# STM32F412VEx-Core.net
KiCad netlist of a schematic drawn in EasyEDA Pro
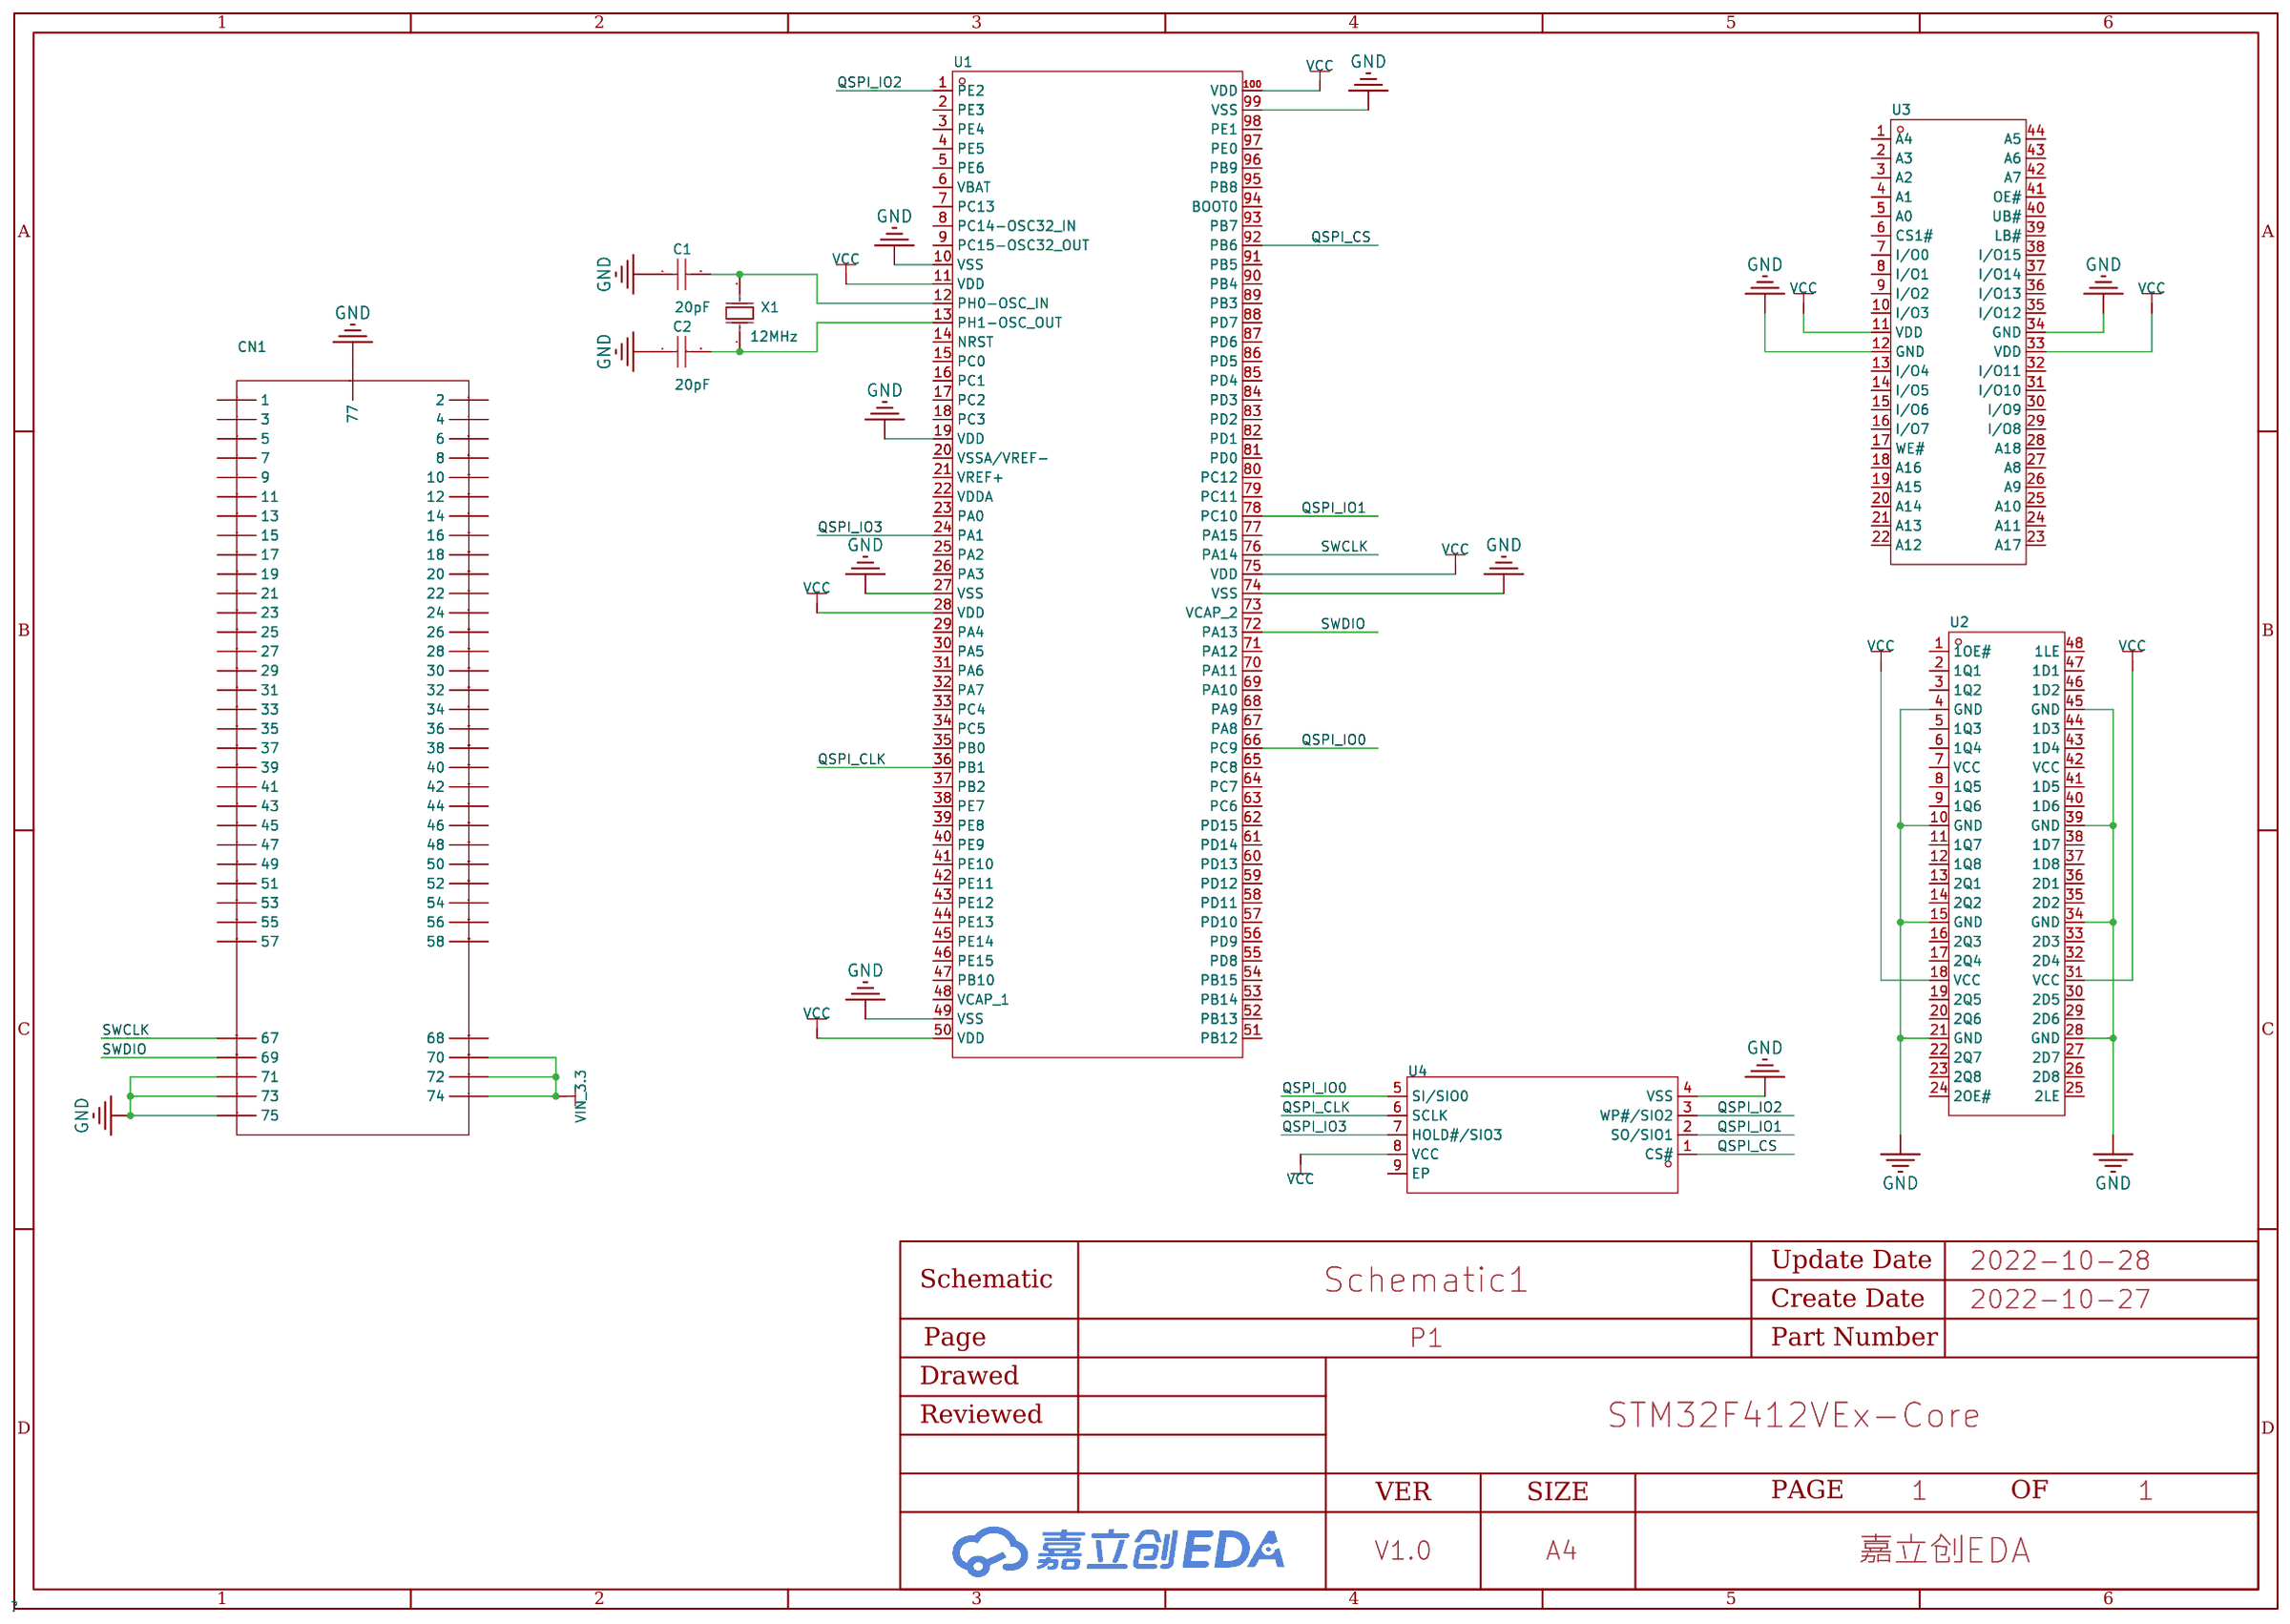
[diagram p0: schematic sheet]

(export (version "E")
  (design (tool "Eeschema 10.0.6"))
  (components
    (comp (ref "C1")
      (value "20pF")
      (footprint "easyedapro:C0402")
      (description "温度系数:C0G;容值:20pF;精度:±5%;额定电压:50V;")
      (fields (field (name "Manufacturer Part") "0402CG200J500NT") (field (name "Manufacturer") "FH(风华)"))
      (libsource (lib "easyedapro") (part "0402CG200J500NT"))
    )
    (comp (ref "C2")
      (value "20pF")
      (footprint "easyedapro:C0402")
      (description "温度系数:C0G;容值:20pF;精度:±5%;额定电压:50V;")
      (fields (field (name "Manufacturer Part") "0402CG200J500NT") (field (name "Manufacturer") "FH(风华)"))
      (libsource (lib "easyedapro") (part "0402CG200J500NT"))
    )
    (comp (ref "CN1")
      (value "~")
      (footprint "easyedapro:M.2_67P_0.5mm_M-key")
      (libsource (lib "easyedapro") (part "M.2_67P_0.5mm_M-key"))
    )
    (comp (ref "U1")
      (value "STM32F412VET6")
      (footprint "easyedapro:LQFP-100_L14.0-W14.0-P0.50-LS16.0-BL")
      (fields (field (name "Manufacturer") "ST(意法半导体)"))
      (libsource (lib "easyedapro") (part "STM32F412VET6"))
    )
    (comp (ref "U2")
      (value "SN74ALVCH16373DGGR")
      (footprint "easyedapro:TSSOP-48_L12.6-W6.2-P0.50-LS8.1-BL")
      (description "系列:74ALVCH;逻辑类型:D 型透明锁存器;输出类型:三态;电压-电源:1.65V ~ 3.6V;")
      (fields (field (name "Manufacturer") "TI(德州仪器)"))
      (libsource (lib "easyedapro") (part "SN74ALVCH16373DGGR"))
    )
    (comp (ref "U3")
      (value "IS62WV51216EBLL-45TLI")
      (footprint "easyedapro:TSOPII-44_L18.4-W10.2-P0.80-LS11.8-BL")
      (fields (field (name "Manufacturer") "ISSI(美国芯成)"))
      (libsource (lib "easyedapro") (part "IS62WV51216EBLL-45TLI"))
    )
    (comp (ref "U4")
      (value "XT26Q01DWSIGA")
      (footprint "easyedapro:WSON-8_L8.0-W6.0-P1.27-TL-EP-1")
      (fields (field (name "Manufacturer") "XTX(芯天下)"))
      (libsource (lib "easyedapro") (part "XT26Q01DWSIGA"))
    )
    (comp (ref "X1")
      (value "12MHz")
      (footprint "easyedapro:OSC-SMD_L5.0-W3.2")
      (description "晶振类型:贴片无源晶振;频率:12MHz;频率公差:±10ppm;频率稳定度:±50ppm;负载电容:20pF;工作温度:-40~+85;")
      (fields (field (name "Manufacturer Part") "X503212MSB2GI") (field (name "Manufacturer") "YXC(扬兴晶振)"))
      (libsource (lib "easyedapro") (part "X503212MSB2GI"))
    )
  )
  (nets
    (net (code "1") (name "/QSPI_CLK") (class "Default")
      (node (ref "U1") (pin "36") (pinfunction "PB1_36") (pintype "input"))
      (node (ref "U4") (pin "6") (pinfunction "SCLK_6") (pintype "input"))
    )
    (net (code "2") (name "/QSPI_CS") (class "Default")
      (node (ref "U1") (pin "92") (pinfunction "PB6_92") (pintype "input"))
      (node (ref "U4") (pin "1") (pinfunction "CS#_1") (pintype "input"))
    )
    (net (code "3") (name "/QSPI_IO0") (class "Default")
      (node (ref "U1") (pin "66") (pinfunction "PC9_66") (pintype "input"))
      (node (ref "U4") (pin "5") (pinfunction "SI/SIO0_5") (pintype "input"))
    )
    (net (code "4") (name "/QSPI_IO1") (class "Default")
      (node (ref "U1") (pin "78") (pinfunction "PC10_78") (pintype "input"))
      (node (ref "U4") (pin "2") (pinfunction "SO/SIO1_2") (pintype "input"))
    )
    (net (code "5") (name "/QSPI_IO2") (class "Default")
      (node (ref "U1") (pin "1") (pinfunction "PE2_1") (pintype "input"))
      (node (ref "U4") (pin "3") (pinfunction "WP#/SIO2_3") (pintype "input"))
    )
    (net (code "6") (name "/QSPI_IO3") (class "Default")
      (node (ref "U1") (pin "24") (pinfunction "PA1_24") (pintype "input"))
      (node (ref "U4") (pin "7") (pinfunction "HOLD#/SIO3_7") (pintype "input"))
    )
    (net (code "7") (name "/SWCLK") (class "Default")
      (node (ref "CN1") (pin "67") (pinfunction "67_67") (pintype "input"))
      (node (ref "U1") (pin "76") (pinfunction "PA14_76") (pintype "input"))
    )
    (net (code "8") (name "/SWDIO") (class "Default")
      (node (ref "CN1") (pin "69") (pinfunction "69_69") (pintype "input"))
      (node (ref "U1") (pin "72") (pinfunction "PA13_72") (pintype "input"))
    )
    (net (code "9") (name "GND") (class "Default")
      (node (ref "C1") (pin "1") (pinfunction "1_1") (pintype "input"))
      (node (ref "C2") (pin "1") (pinfunction "1_1") (pintype "input"))
      (node (ref "CN1") (pin "71") (pinfunction "71_71") (pintype "input"))
      (node (ref "CN1") (pin "73") (pinfunction "73_73") (pintype "input"))
      (node (ref "CN1") (pin "75") (pinfunction "75_75") (pintype "input"))
      (node (ref "CN1") (pin "77") (pinfunction "77_77") (pintype "input"))
      (node (ref "U1") (pin "10") (pinfunction "VSS_10") (pintype "input"))
      (node (ref "U1") (pin "19") (pinfunction "VDD_19") (pintype "input"))
      (node (ref "U1") (pin "27") (pinfunction "VSS_27") (pintype "input"))
      (node (ref "U1") (pin "49") (pinfunction "VSS_49") (pintype "input"))
      (node (ref "U1") (pin "74") (pinfunction "VSS_74") (pintype "input"))
      (node (ref "U1") (pin "99") (pinfunction "VSS_99") (pintype "input"))
      (node (ref "U2") (pin "10") (pinfunction "GND_10") (pintype "input"))
      (node (ref "U2") (pin "15") (pinfunction "GND_15") (pintype "input"))
      (node (ref "U2") (pin "21") (pinfunction "GND_21") (pintype "input"))
      (node (ref "U2") (pin "28") (pinfunction "GND_28") (pintype "input"))
      (node (ref "U2") (pin "34") (pinfunction "GND_34") (pintype "input"))
      (node (ref "U2") (pin "39") (pinfunction "GND_39") (pintype "input"))
      (node (ref "U2") (pin "4") (pinfunction "GND_4") (pintype "input"))
      (node (ref "U2") (pin "45") (pinfunction "GND_45") (pintype "input"))
      (node (ref "U3") (pin "12") (pinfunction "GND_12") (pintype "input"))
      (node (ref "U3") (pin "34") (pinfunction "GND_34") (pintype "input"))
      (node (ref "U4") (pin "4") (pinfunction "VSS_4") (pintype "input"))
    )
    (net (code "10") (name "Net-(U1-PH0-OSC_IN)") (class "Default")
      (node (ref "C1") (pin "2") (pinfunction "2_2") (pintype "input"))
      (node (ref "U1") (pin "12") (pinfunction "PH0-OSC_IN_12") (pintype "input"))
      (node (ref "X1") (pin "2") (pinfunction "OSC2_2") (pintype "input"))
    )
    (net (code "11") (name "Net-(U1-PH1-OSC_OUT)") (class "Default")
      (node (ref "C2") (pin "2") (pinfunction "2_2") (pintype "input"))
      (node (ref "U1") (pin "13") (pinfunction "PH1-OSC_OUT_13") (pintype "input"))
      (node (ref "X1") (pin "1") (pinfunction "OSC1_1") (pintype "input"))
    )
    (net (code "12") (name "VCC") (class "Default")
      (node (ref "U1") (pin "100") (pinfunction "VDD_100") (pintype "input"))
      (node (ref "U1") (pin "11") (pinfunction "VDD_11") (pintype "input"))
      (node (ref "U1") (pin "28") (pinfunction "VDD_28") (pintype "input"))
      (node (ref "U1") (pin "50") (pinfunction "VDD_50") (pintype "input"))
      (node (ref "U1") (pin "75") (pinfunction "VDD_75") (pintype "input"))
      (node (ref "U2") (pin "18") (pinfunction "VCC_18") (pintype "input"))
      (node (ref "U2") (pin "31") (pinfunction "VCC_31") (pintype "input"))
      (node (ref "U3") (pin "11") (pinfunction "VDD_11") (pintype "input"))
      (node (ref "U3") (pin "33") (pinfunction "VDD_33") (pintype "input"))
      (node (ref "U4") (pin "8") (pinfunction "VCC_8") (pintype "input"))
    )
    (net (code "13") (name "VIN_3.3") (class "Default")
      (node (ref "CN1") (pin "70") (pinfunction "70_70") (pintype "input"))
      (node (ref "CN1") (pin "72") (pinfunction "72_72") (pintype "input"))
      (node (ref "CN1") (pin "74") (pinfunction "74_74") (pintype "input"))
    )
    (net (code "14") (name "unconnected-(CN1-Pad1)") (class "Default")
      (node (ref "CN1") (pin "1") (pinfunction "1_1") (pintype "input"))
    )
    (net (code "15") (name "unconnected-(CN1-Pad2)") (class "Default")
      (node (ref "CN1") (pin "2") (pinfunction "2_2") (pintype "input"))
    )
    (net (code "16") (name "unconnected-(CN1-Pad3)") (class "Default")
      (node (ref "CN1") (pin "3") (pinfunction "3_3") (pintype "input"))
    )
    (net (code "17") (name "unconnected-(CN1-Pad4)") (class "Default")
      (node (ref "CN1") (pin "4") (pinfunction "4_4") (pintype "input"))
    )
    (net (code "18") (name "unconnected-(CN1-Pad5)") (class "Default")
      (node (ref "CN1") (pin "5") (pinfunction "5_5") (pintype "input"))
    )
    (net (code "19") (name "unconnected-(CN1-Pad6)") (class "Default")
      (node (ref "CN1") (pin "6") (pinfunction "6_6") (pintype "input"))
    )
    (net (code "20") (name "unconnected-(CN1-Pad7)") (class "Default")
      (node (ref "CN1") (pin "7") (pinfunction "7_7") (pintype "input"))
    )
    (net (code "21") (name "unconnected-(CN1-Pad8)") (class "Default")
      (node (ref "CN1") (pin "8") (pinfunction "8_8") (pintype "input"))
    )
    (net (code "22") (name "unconnected-(CN1-Pad9)") (class "Default")
      (node (ref "CN1") (pin "9") (pinfunction "9_9") (pintype "input"))
    )
    (net (code "23") (name "unconnected-(CN1-Pad10)") (class "Default")
      (node (ref "CN1") (pin "10") (pinfunction "10_10") (pintype "input"))
    )
    (net (code "24") (name "unconnected-(CN1-Pad11)") (class "Default")
      (node (ref "CN1") (pin "11") (pinfunction "11_11") (pintype "input"))
    )
    (net (code "25") (name "unconnected-(CN1-Pad12)") (class "Default")
      (node (ref "CN1") (pin "12") (pinfunction "12_12") (pintype "input"))
    )
    (net (code "26") (name "unconnected-(CN1-Pad13)") (class "Default")
      (node (ref "CN1") (pin "13") (pinfunction "13_13") (pintype "input"))
    )
    (net (code "27") (name "unconnected-(CN1-Pad14)") (class "Default")
      (node (ref "CN1") (pin "14") (pinfunction "14_14") (pintype "input"))
    )
    (net (code "28") (name "unconnected-(CN1-Pad15)") (class "Default")
      (node (ref "CN1") (pin "15") (pinfunction "15_15") (pintype "input"))
    )
    (net (code "29") (name "unconnected-(CN1-Pad16)") (class "Default")
      (node (ref "CN1") (pin "16") (pinfunction "16_16") (pintype "input"))
    )
    (net (code "30") (name "unconnected-(CN1-Pad17)") (class "Default")
      (node (ref "CN1") (pin "17") (pinfunction "17_17") (pintype "input"))
    )
    (net (code "31") (name "unconnected-(CN1-Pad18)") (class "Default")
      (node (ref "CN1") (pin "18") (pinfunction "18_18") (pintype "input"))
    )
    (net (code "32") (name "unconnected-(CN1-Pad19)") (class "Default")
      (node (ref "CN1") (pin "19") (pinfunction "19_19") (pintype "input"))
    )
    (net (code "33") (name "unconnected-(CN1-Pad20)") (class "Default")
      (node (ref "CN1") (pin "20") (pinfunction "20_20") (pintype "input"))
    )
    (net (code "34") (name "unconnected-(CN1-Pad21)") (class "Default")
      (node (ref "CN1") (pin "21") (pinfunction "21_21") (pintype "input"))
    )
    (net (code "35") (name "unconnected-(CN1-Pad22)") (class "Default")
      (node (ref "CN1") (pin "22") (pinfunction "22_22") (pintype "input"))
    )
    (net (code "36") (name "unconnected-(CN1-Pad23)") (class "Default")
      (node (ref "CN1") (pin "23") (pinfunction "23_23") (pintype "input"))
    )
    (net (code "37") (name "unconnected-(CN1-Pad24)") (class "Default")
      (node (ref "CN1") (pin "24") (pinfunction "24_24") (pintype "input"))
    )
    (net (code "38") (name "unconnected-(CN1-Pad25)") (class "Default")
      (node (ref "CN1") (pin "25") (pinfunction "25_25") (pintype "input"))
    )
    (net (code "39") (name "unconnected-(CN1-Pad26)") (class "Default")
      (node (ref "CN1") (pin "26") (pinfunction "26_26") (pintype "input"))
    )
    (net (code "40") (name "unconnected-(CN1-Pad27)") (class "Default")
      (node (ref "CN1") (pin "27") (pinfunction "27_27") (pintype "input"))
    )
    (net (code "41") (name "unconnected-(CN1-Pad28)") (class "Default")
      (node (ref "CN1") (pin "28") (pinfunction "28_28") (pintype "input"))
    )
    (net (code "42") (name "unconnected-(CN1-Pad29)") (class "Default")
      (node (ref "CN1") (pin "29") (pinfunction "29_29") (pintype "input"))
    )
    (net (code "43") (name "unconnected-(CN1-Pad30)") (class "Default")
      (node (ref "CN1") (pin "30") (pinfunction "30_30") (pintype "input"))
    )
    (net (code "44") (name "unconnected-(CN1-Pad31)") (class "Default")
      (node (ref "CN1") (pin "31") (pinfunction "31_31") (pintype "input"))
    )
    (net (code "45") (name "unconnected-(CN1-Pad32)") (class "Default")
      (node (ref "CN1") (pin "32") (pinfunction "32_32") (pintype "input"))
    )
    (net (code "46") (name "unconnected-(CN1-Pad33)") (class "Default")
      (node (ref "CN1") (pin "33") (pinfunction "33_33") (pintype "input"))
    )
    (net (code "47") (name "unconnected-(CN1-Pad34)") (class "Default")
      (node (ref "CN1") (pin "34") (pinfunction "34_34") (pintype "input"))
    )
    (net (code "48") (name "unconnected-(CN1-Pad35)") (class "Default")
      (node (ref "CN1") (pin "35") (pinfunction "35_35") (pintype "input"))
    )
    (net (code "49") (name "unconnected-(CN1-Pad36)") (class "Default")
      (node (ref "CN1") (pin "36") (pinfunction "36_36") (pintype "input"))
    )
    (net (code "50") (name "unconnected-(CN1-Pad37)") (class "Default")
      (node (ref "CN1") (pin "37") (pinfunction "37_37") (pintype "input"))
    )
    (net (code "51") (name "unconnected-(CN1-Pad38)") (class "Default")
      (node (ref "CN1") (pin "38") (pinfunction "38_38") (pintype "input"))
    )
    (net (code "52") (name "unconnected-(CN1-Pad39)") (class "Default")
      (node (ref "CN1") (pin "39") (pinfunction "39_39") (pintype "input"))
    )
    (net (code "53") (name "unconnected-(CN1-Pad40)") (class "Default")
      (node (ref "CN1") (pin "40") (pinfunction "40_40") (pintype "input"))
    )
    (net (code "54") (name "unconnected-(CN1-Pad41)") (class "Default")
      (node (ref "CN1") (pin "41") (pinfunction "41_41") (pintype "input"))
    )
    (net (code "55") (name "unconnected-(CN1-Pad42)") (class "Default")
      (node (ref "CN1") (pin "42") (pinfunction "42_42") (pintype "input"))
    )
    (net (code "56") (name "unconnected-(CN1-Pad43)") (class "Default")
      (node (ref "CN1") (pin "43") (pinfunction "43_43") (pintype "input"))
    )
    (net (code "57") (name "unconnected-(CN1-Pad44)") (class "Default")
      (node (ref "CN1") (pin "44") (pinfunction "44_44") (pintype "input"))
    )
    (net (code "58") (name "unconnected-(CN1-Pad45)") (class "Default")
      (node (ref "CN1") (pin "45") (pinfunction "45_45") (pintype "input"))
    )
    (net (code "59") (name "unconnected-(CN1-Pad46)") (class "Default")
      (node (ref "CN1") (pin "46") (pinfunction "46_46") (pintype "input"))
    )
    (net (code "60") (name "unconnected-(CN1-Pad47)") (class "Default")
      (node (ref "CN1") (pin "47") (pinfunction "47_47") (pintype "input"))
    )
    (net (code "61") (name "unconnected-(CN1-Pad48)") (class "Default")
      (node (ref "CN1") (pin "48") (pinfunction "48_48") (pintype "input"))
    )
    (net (code "62") (name "unconnected-(CN1-Pad49)") (class "Default")
      (node (ref "CN1") (pin "49") (pinfunction "49_49") (pintype "input"))
    )
    (net (code "63") (name "unconnected-(CN1-Pad50)") (class "Default")
      (node (ref "CN1") (pin "50") (pinfunction "50_50") (pintype "input"))
    )
    (net (code "64") (name "unconnected-(CN1-Pad51)") (class "Default")
      (node (ref "CN1") (pin "51") (pinfunction "51_51") (pintype "input"))
    )
    (net (code "65") (name "unconnected-(CN1-Pad52)") (class "Default")
      (node (ref "CN1") (pin "52") (pinfunction "52_52") (pintype "input"))
    )
    (net (code "66") (name "unconnected-(CN1-Pad53)") (class "Default")
      (node (ref "CN1") (pin "53") (pinfunction "53_53") (pintype "input"))
    )
    (net (code "67") (name "unconnected-(CN1-Pad54)") (class "Default")
      (node (ref "CN1") (pin "54") (pinfunction "54_54") (pintype "input"))
    )
    (net (code "68") (name "unconnected-(CN1-Pad55)") (class "Default")
      (node (ref "CN1") (pin "55") (pinfunction "55_55") (pintype "input"))
    )
    (net (code "69") (name "unconnected-(CN1-Pad56)") (class "Default")
      (node (ref "CN1") (pin "56") (pinfunction "56_56") (pintype "input"))
    )
    (net (code "70") (name "unconnected-(CN1-Pad57)") (class "Default")
      (node (ref "CN1") (pin "57") (pinfunction "57_57") (pintype "input"))
    )
    (net (code "71") (name "unconnected-(CN1-Pad58)") (class "Default")
      (node (ref "CN1") (pin "58") (pinfunction "58_58") (pintype "input"))
    )
    (net (code "72") (name "unconnected-(CN1-Pad68)") (class "Default")
      (node (ref "CN1") (pin "68") (pinfunction "68_68") (pintype "input"))
    )
    (net (code "73") (name "unconnected-(U1-BOOT0-Pad94)") (class "Default")
      (node (ref "U1") (pin "94") (pinfunction "BOOT0_94") (pintype "input"))
    )
    (net (code "74") (name "unconnected-(U1-NRST-Pad14)") (class "Default")
      (node (ref "U1") (pin "14") (pinfunction "NRST_14") (pintype "input"))
    )
    (net (code "75") (name "unconnected-(U1-PA0-Pad23)") (class "Default")
      (node (ref "U1") (pin "23") (pinfunction "PA0_23") (pintype "input"))
    )
    (net (code "76") (name "unconnected-(U1-PA2-Pad25)") (class "Default")
      (node (ref "U1") (pin "25") (pinfunction "PA2_25") (pintype "input"))
    )
    (net (code "77") (name "unconnected-(U1-PA3-Pad26)") (class "Default")
      (node (ref "U1") (pin "26") (pinfunction "PA3_26") (pintype "input"))
    )
    (net (code "78") (name "unconnected-(U1-PA4-Pad29)") (class "Default")
      (node (ref "U1") (pin "29") (pinfunction "PA4_29") (pintype "input"))
    )
    (net (code "79") (name "unconnected-(U1-PA5-Pad30)") (class "Default")
      (node (ref "U1") (pin "30") (pinfunction "PA5_30") (pintype "input"))
    )
    (net (code "80") (name "unconnected-(U1-PA6-Pad31)") (class "Default")
      (node (ref "U1") (pin "31") (pinfunction "PA6_31") (pintype "input"))
    )
    (net (code "81") (name "unconnected-(U1-PA7-Pad32)") (class "Default")
      (node (ref "U1") (pin "32") (pinfunction "PA7_32") (pintype "input"))
    )
    (net (code "82") (name "unconnected-(U1-PA8-Pad67)") (class "Default")
      (node (ref "U1") (pin "67") (pinfunction "PA8_67") (pintype "input"))
    )
    (net (code "83") (name "unconnected-(U1-PA9-Pad68)") (class "Default")
      (node (ref "U1") (pin "68") (pinfunction "PA9_68") (pintype "input"))
    )
    (net (code "84") (name "unconnected-(U1-PA10-Pad69)") (class "Default")
      (node (ref "U1") (pin "69") (pinfunction "PA10_69") (pintype "input"))
    )
    (net (code "85") (name "unconnected-(U1-PA11-Pad70)") (class "Default")
      (node (ref "U1") (pin "70") (pinfunction "PA11_70") (pintype "input"))
    )
    (net (code "86") (name "unconnected-(U1-PA12-Pad71)") (class "Default")
      (node (ref "U1") (pin "71") (pinfunction "PA12_71") (pintype "input"))
    )
    (net (code "87") (name "unconnected-(U1-PA15-Pad77)") (class "Default")
      (node (ref "U1") (pin "77") (pinfunction "PA15_77") (pintype "input"))
    )
    (net (code "88") (name "unconnected-(U1-PB0-Pad35)") (class "Default")
      (node (ref "U1") (pin "35") (pinfunction "PB0_35") (pintype "input"))
    )
    (net (code "89") (name "unconnected-(U1-PB2-Pad37)") (class "Default")
      (node (ref "U1") (pin "37") (pinfunction "PB2_37") (pintype "input"))
    )
    (net (code "90") (name "unconnected-(U1-PB3-Pad89)") (class "Default")
      (node (ref "U1") (pin "89") (pinfunction "PB3_89") (pintype "input"))
    )
    (net (code "91") (name "unconnected-(U1-PB4-Pad90)") (class "Default")
      (node (ref "U1") (pin "90") (pinfunction "PB4_90") (pintype "input"))
    )
    (net (code "92") (name "unconnected-(U1-PB5-Pad91)") (class "Default")
      (node (ref "U1") (pin "91") (pinfunction "PB5_91") (pintype "input"))
    )
    (net (code "93") (name "unconnected-(U1-PB7-Pad93)") (class "Default")
      (node (ref "U1") (pin "93") (pinfunction "PB7_93") (pintype "input"))
    )
    (net (code "94") (name "unconnected-(U1-PB8-Pad95)") (class "Default")
      (node (ref "U1") (pin "95") (pinfunction "PB8_95") (pintype "input"))
    )
    (net (code "95") (name "unconnected-(U1-PB9-Pad96)") (class "Default")
      (node (ref "U1") (pin "96") (pinfunction "PB9_96") (pintype "input"))
    )
    (net (code "96") (name "unconnected-(U1-PB10-Pad47)") (class "Default")
      (node (ref "U1") (pin "47") (pinfunction "PB10_47") (pintype "input"))
    )
    (net (code "97") (name "unconnected-(U1-PB12-Pad51)") (class "Default")
      (node (ref "U1") (pin "51") (pinfunction "PB12_51") (pintype "input"))
    )
    (net (code "98") (name "unconnected-(U1-PB13-Pad52)") (class "Default")
      (node (ref "U1") (pin "52") (pinfunction "PB13_52") (pintype "input"))
    )
    (net (code "99") (name "unconnected-(U1-PB14-Pad53)") (class "Default")
      (node (ref "U1") (pin "53") (pinfunction "PB14_53") (pintype "input"))
    )
    (net (code "100") (name "unconnected-(U1-PB15-Pad54)") (class "Default")
      (node (ref "U1") (pin "54") (pinfunction "PB15_54") (pintype "input"))
    )
    (net (code "101") (name "unconnected-(U1-PC0-Pad15)") (class "Default")
      (node (ref "U1") (pin "15") (pinfunction "PC0_15") (pintype "input"))
    )
    (net (code "102") (name "unconnected-(U1-PC1-Pad16)") (class "Default")
      (node (ref "U1") (pin "16") (pinfunction "PC1_16") (pintype "input"))
    )
    (net (code "103") (name "unconnected-(U1-PC2-Pad17)") (class "Default")
      (node (ref "U1") (pin "17") (pinfunction "PC2_17") (pintype "input"))
    )
    (net (code "104") (name "unconnected-(U1-PC3-Pad18)") (class "Default")
      (node (ref "U1") (pin "18") (pinfunction "PC3_18") (pintype "input"))
    )
    (net (code "105") (name "unconnected-(U1-PC4-Pad33)") (class "Default")
      (node (ref "U1") (pin "33") (pinfunction "PC4_33") (pintype "input"))
    )
    (net (code "106") (name "unconnected-(U1-PC5-Pad34)") (class "Default")
      (node (ref "U1") (pin "34") (pinfunction "PC5_34") (pintype "input"))
    )
    (net (code "107") (name "unconnected-(U1-PC6-Pad63)") (class "Default")
      (node (ref "U1") (pin "63") (pinfunction "PC6_63") (pintype "input"))
    )
    (net (code "108") (name "unconnected-(U1-PC7-Pad64)") (class "Default")
      (node (ref "U1") (pin "64") (pinfunction "PC7_64") (pintype "input"))
    )
    (net (code "109") (name "unconnected-(U1-PC8-Pad65)") (class "Default")
      (node (ref "U1") (pin "65") (pinfunction "PC8_65") (pintype "input"))
    )
    (net (code "110") (name "unconnected-(U1-PC11-Pad79)") (class "Default")
      (node (ref "U1") (pin "79") (pinfunction "PC11_79") (pintype "input"))
    )
    (net (code "111") (name "unconnected-(U1-PC12-Pad80)") (class "Default")
      (node (ref "U1") (pin "80") (pinfunction "PC12_80") (pintype "input"))
    )
    (net (code "112") (name "unconnected-(U1-PC13-Pad7)") (class "Default")
      (node (ref "U1") (pin "7") (pinfunction "PC13_7") (pintype "input"))
    )
    (net (code "113") (name "unconnected-(U1-PC14-OSC32_IN-Pad8)") (class "Default")
      (node (ref "U1") (pin "8") (pinfunction "PC14-OSC32_IN_8") (pintype "input"))
    )
    (net (code "114") (name "unconnected-(U1-PC15-OSC32_OUT-Pad9)") (class "Default")
      (node (ref "U1") (pin "9") (pinfunction "PC15-OSC32_OUT_9") (pintype "input"))
    )
    (net (code "115") (name "unconnected-(U1-PD0-Pad81)") (class "Default")
      (node (ref "U1") (pin "81") (pinfunction "PD0_81") (pintype "input"))
    )
    (net (code "116") (name "unconnected-(U1-PD1-Pad82)") (class "Default")
      (node (ref "U1") (pin "82") (pinfunction "PD1_82") (pintype "input"))
    )
    (net (code "117") (name "unconnected-(U1-PD2-Pad83)") (class "Default")
      (node (ref "U1") (pin "83") (pinfunction "PD2_83") (pintype "input"))
    )
    (net (code "118") (name "unconnected-(U1-PD3-Pad84)") (class "Default")
      (node (ref "U1") (pin "84") (pinfunction "PD3_84") (pintype "input"))
    )
    (net (code "119") (name "unconnected-(U1-PD4-Pad85)") (class "Default")
      (node (ref "U1") (pin "85") (pinfunction "PD4_85") (pintype "input"))
    )
    (net (code "120") (name "unconnected-(U1-PD5-Pad86)") (class "Default")
      (node (ref "U1") (pin "86") (pinfunction "PD5_86") (pintype "input"))
    )
    (net (code "121") (name "unconnected-(U1-PD6-Pad87)") (class "Default")
      (node (ref "U1") (pin "87") (pinfunction "PD6_87") (pintype "input"))
    )
    (net (code "122") (name "unconnected-(U1-PD7-Pad88)") (class "Default")
      (node (ref "U1") (pin "88") (pinfunction "PD7_88") (pintype "input"))
    )
    (net (code "123") (name "unconnected-(U1-PD8-Pad55)") (class "Default")
      (node (ref "U1") (pin "55") (pinfunction "PD8_55") (pintype "input"))
    )
    (net (code "124") (name "unconnected-(U1-PD9-Pad56)") (class "Default")
      (node (ref "U1") (pin "56") (pinfunction "PD9_56") (pintype "input"))
    )
    (net (code "125") (name "unconnected-(U1-PD10-Pad57)") (class "Default")
      (node (ref "U1") (pin "57") (pinfunction "PD10_57") (pintype "input"))
    )
    (net (code "126") (name "unconnected-(U1-PD11-Pad58)") (class "Default")
      (node (ref "U1") (pin "58") (pinfunction "PD11_58") (pintype "input"))
    )
    (net (code "127") (name "unconnected-(U1-PD12-Pad59)") (class "Default")
      (node (ref "U1") (pin "59") (pinfunction "PD12_59") (pintype "input"))
    )
    (net (code "128") (name "unconnected-(U1-PD13-Pad60)") (class "Default")
      (node (ref "U1") (pin "60") (pinfunction "PD13_60") (pintype "input"))
    )
    (net (code "129") (name "unconnected-(U1-PD14-Pad61)") (class "Default")
      (node (ref "U1") (pin "61") (pinfunction "PD14_61") (pintype "input"))
    )
    (net (code "130") (name "unconnected-(U1-PD15-Pad62)") (class "Default")
      (node (ref "U1") (pin "62") (pinfunction "PD15_62") (pintype "input"))
    )
    (net (code "131") (name "unconnected-(U1-PE0-Pad97)") (class "Default")
      (node (ref "U1") (pin "97") (pinfunction "PE0_97") (pintype "input"))
    )
    (net (code "132") (name "unconnected-(U1-PE1-Pad98)") (class "Default")
      (node (ref "U1") (pin "98") (pinfunction "PE1_98") (pintype "input"))
    )
    (net (code "133") (name "unconnected-(U1-PE3-Pad2)") (class "Default")
      (node (ref "U1") (pin "2") (pinfunction "PE3_2") (pintype "input"))
    )
    (net (code "134") (name "unconnected-(U1-PE4-Pad3)") (class "Default")
      (node (ref "U1") (pin "3") (pinfunction "PE4_3") (pintype "input"))
    )
    (net (code "135") (name "unconnected-(U1-PE5-Pad4)") (class "Default")
      (node (ref "U1") (pin "4") (pinfunction "PE5_4") (pintype "input"))
    )
    (net (code "136") (name "unconnected-(U1-PE6-Pad5)") (class "Default")
      (node (ref "U1") (pin "5") (pinfunction "PE6_5") (pintype "input"))
    )
    (net (code "137") (name "unconnected-(U1-PE7-Pad38)") (class "Default")
      (node (ref "U1") (pin "38") (pinfunction "PE7_38") (pintype "input"))
    )
    (net (code "138") (name "unconnected-(U1-PE8-Pad39)") (class "Default")
      (node (ref "U1") (pin "39") (pinfunction "PE8_39") (pintype "input"))
    )
    (net (code "139") (name "unconnected-(U1-PE9-Pad40)") (class "Default")
      (node (ref "U1") (pin "40") (pinfunction "PE9_40") (pintype "input"))
    )
    (net (code "140") (name "unconnected-(U1-PE10-Pad41)") (class "Default")
      (node (ref "U1") (pin "41") (pinfunction "PE10_41") (pintype "input"))
    )
    (net (code "141") (name "unconnected-(U1-PE11-Pad42)") (class "Default")
      (node (ref "U1") (pin "42") (pinfunction "PE11_42") (pintype "input"))
    )
    (net (code "142") (name "unconnected-(U1-PE12-Pad43)") (class "Default")
      (node (ref "U1") (pin "43") (pinfunction "PE12_43") (pintype "input"))
    )
    (net (code "143") (name "unconnected-(U1-PE13-Pad44)") (class "Default")
      (node (ref "U1") (pin "44") (pinfunction "PE13_44") (pintype "input"))
    )
    (net (code "144") (name "unconnected-(U1-PE14-Pad45)") (class "Default")
      (node (ref "U1") (pin "45") (pinfunction "PE14_45") (pintype "input"))
    )
    (net (code "145") (name "unconnected-(U1-PE15-Pad46)") (class "Default")
      (node (ref "U1") (pin "46") (pinfunction "PE15_46") (pintype "input"))
    )
    (net (code "146") (name "unconnected-(U1-VBAT-Pad6)") (class "Default")
      (node (ref "U1") (pin "6") (pinfunction "VBAT_6") (pintype "input"))
    )
    (net (code "147") (name "unconnected-(U1-VCAP_1-Pad48)") (class "Default")
      (node (ref "U1") (pin "48") (pinfunction "VCAP_1_48") (pintype "input"))
    )
    (net (code "148") (name "unconnected-(U1-VCAP_2-Pad73)") (class "Default")
      (node (ref "U1") (pin "73") (pinfunction "VCAP_2_73") (pintype "input"))
    )
    (net (code "149") (name "unconnected-(U1-VDDA-Pad22)") (class "Default")
      (node (ref "U1") (pin "22") (pinfunction "VDDA_22") (pintype "input"))
    )
    (net (code "150") (name "unconnected-(U1-VREF+-Pad21)") (class "Default")
      (node (ref "U1") (pin "21") (pinfunction "VREF+_21") (pintype "input"))
    )
    (net (code "151") (name "unconnected-(U1-VSSA{slash}VREF--Pad20)") (class "Default")
      (node (ref "U1") (pin "20") (pinfunction "VSSA/VREF-_20") (pintype "input"))
    )
    (net (code "152") (name "unconnected-(U2-1D1-Pad47)") (class "Default")
      (node (ref "U2") (pin "47") (pinfunction "1D1_47") (pintype "input"))
    )
    (net (code "153") (name "unconnected-(U2-1D2-Pad46)") (class "Default")
      (node (ref "U2") (pin "46") (pinfunction "1D2_46") (pintype "input"))
    )
    (net (code "154") (name "unconnected-(U2-1D3-Pad44)") (class "Default")
      (node (ref "U2") (pin "44") (pinfunction "1D3_44") (pintype "input"))
    )
    (net (code "155") (name "unconnected-(U2-1D4-Pad43)") (class "Default")
      (node (ref "U2") (pin "43") (pinfunction "1D4_43") (pintype "input"))
    )
    (net (code "156") (name "unconnected-(U2-1D5-Pad41)") (class "Default")
      (node (ref "U2") (pin "41") (pinfunction "1D5_41") (pintype "input"))
    )
    (net (code "157") (name "unconnected-(U2-1D6-Pad40)") (class "Default")
      (node (ref "U2") (pin "40") (pinfunction "1D6_40") (pintype "input"))
    )
    (net (code "158") (name "unconnected-(U2-1D7-Pad38)") (class "Default")
      (node (ref "U2") (pin "38") (pinfunction "1D7_38") (pintype "input"))
    )
    (net (code "159") (name "unconnected-(U2-1D8-Pad37)") (class "Default")
      (node (ref "U2") (pin "37") (pinfunction "1D8_37") (pintype "input"))
    )
    (net (code "160") (name "unconnected-(U2-1LE-Pad48)") (class "Default")
      (node (ref "U2") (pin "48") (pinfunction "1LE_48") (pintype "input"))
    )
    (net (code "161") (name "unconnected-(U2-1OE#-Pad1)") (class "Default")
      (node (ref "U2") (pin "1") (pinfunction "1OE#_1") (pintype "input"))
    )
    (net (code "162") (name "unconnected-(U2-1Q1-Pad2)") (class "Default")
      (node (ref "U2") (pin "2") (pinfunction "1Q1_2") (pintype "input"))
    )
    (net (code "163") (name "unconnected-(U2-1Q2-Pad3)") (class "Default")
      (node (ref "U2") (pin "3") (pinfunction "1Q2_3") (pintype "input"))
    )
    (net (code "164") (name "unconnected-(U2-1Q3-Pad5)") (class "Default")
      (node (ref "U2") (pin "5") (pinfunction "1Q3_5") (pintype "input"))
    )
    (net (code "165") (name "unconnected-(U2-1Q4-Pad6)") (class "Default")
      (node (ref "U2") (pin "6") (pinfunction "1Q4_6") (pintype "input"))
    )
    (net (code "166") (name "unconnected-(U2-1Q5-Pad8)") (class "Default")
      (node (ref "U2") (pin "8") (pinfunction "1Q5_8") (pintype "input"))
    )
    (net (code "167") (name "unconnected-(U2-1Q6-Pad9)") (class "Default")
      (node (ref "U2") (pin "9") (pinfunction "1Q6_9") (pintype "input"))
    )
    (net (code "168") (name "unconnected-(U2-1Q7-Pad11)") (class "Default")
      (node (ref "U2") (pin "11") (pinfunction "1Q7_11") (pintype "input"))
    )
    (net (code "169") (name "unconnected-(U2-1Q8-Pad12)") (class "Default")
      (node (ref "U2") (pin "12") (pinfunction "1Q8_12") (pintype "input"))
    )
    (net (code "170") (name "unconnected-(U2-2D1-Pad36)") (class "Default")
      (node (ref "U2") (pin "36") (pinfunction "2D1_36") (pintype "input"))
    )
    (net (code "171") (name "unconnected-(U2-2D2-Pad35)") (class "Default")
      (node (ref "U2") (pin "35") (pinfunction "2D2_35") (pintype "input"))
    )
    (net (code "172") (name "unconnected-(U2-2D3-Pad33)") (class "Default")
      (node (ref "U2") (pin "33") (pinfunction "2D3_33") (pintype "input"))
    )
    (net (code "173") (name "unconnected-(U2-2D4-Pad32)") (class "Default")
      (node (ref "U2") (pin "32") (pinfunction "2D4_32") (pintype "input"))
    )
    (net (code "174") (name "unconnected-(U2-2D5-Pad30)") (class "Default")
      (node (ref "U2") (pin "30") (pinfunction "2D5_30") (pintype "input"))
    )
    (net (code "175") (name "unconnected-(U2-2D6-Pad29)") (class "Default")
      (node (ref "U2") (pin "29") (pinfunction "2D6_29") (pintype "input"))
    )
    (net (code "176") (name "unconnected-(U2-2D7-Pad27)") (class "Default")
      (node (ref "U2") (pin "27") (pinfunction "2D7_27") (pintype "input"))
    )
    (net (code "177") (name "unconnected-(U2-2D8-Pad26)") (class "Default")
      (node (ref "U2") (pin "26") (pinfunction "2D8_26") (pintype "input"))
    )
    (net (code "178") (name "unconnected-(U2-2LE-Pad25)") (class "Default")
      (node (ref "U2") (pin "25") (pinfunction "2LE_25") (pintype "input"))
    )
    (net (code "179") (name "unconnected-(U2-2OE#-Pad24)") (class "Default")
      (node (ref "U2") (pin "24") (pinfunction "2OE#_24") (pintype "input"))
    )
    (net (code "180") (name "unconnected-(U2-2Q1-Pad13)") (class "Default")
      (node (ref "U2") (pin "13") (pinfunction "2Q1_13") (pintype "input"))
    )
    (net (code "181") (name "unconnected-(U2-2Q2-Pad14)") (class "Default")
      (node (ref "U2") (pin "14") (pinfunction "2Q2_14") (pintype "input"))
    )
    (net (code "182") (name "unconnected-(U2-2Q3-Pad16)") (class "Default")
      (node (ref "U2") (pin "16") (pinfunction "2Q3_16") (pintype "input"))
    )
    (net (code "183") (name "unconnected-(U2-2Q4-Pad17)") (class "Default")
      (node (ref "U2") (pin "17") (pinfunction "2Q4_17") (pintype "input"))
    )
    (net (code "184") (name "unconnected-(U2-2Q5-Pad19)") (class "Default")
      (node (ref "U2") (pin "19") (pinfunction "2Q5_19") (pintype "input"))
    )
    (net (code "185") (name "unconnected-(U2-2Q6-Pad20)") (class "Default")
      (node (ref "U2") (pin "20") (pinfunction "2Q6_20") (pintype "input"))
    )
    (net (code "186") (name "unconnected-(U2-2Q7-Pad22)") (class "Default")
      (node (ref "U2") (pin "22") (pinfunction "2Q7_22") (pintype "input"))
    )
    (net (code "187") (name "unconnected-(U2-2Q8-Pad23)") (class "Default")
      (node (ref "U2") (pin "23") (pinfunction "2Q8_23") (pintype "input"))
    )
    (net (code "188") (name "unconnected-(U2-VCC-Pad7)") (class "Default")
      (node (ref "U2") (pin "7") (pinfunction "VCC_7") (pintype "input"))
    )
    (net (code "189") (name "unconnected-(U2-VCC-Pad42)") (class "Default")
      (node (ref "U2") (pin "42") (pinfunction "VCC_42") (pintype "input"))
    )
    (net (code "190") (name "unconnected-(U3-A0-Pad5)") (class "Default")
      (node (ref "U3") (pin "5") (pinfunction "A0_5") (pintype "input"))
    )
    (net (code "191") (name "unconnected-(U3-A1-Pad4)") (class "Default")
      (node (ref "U3") (pin "4") (pinfunction "A1_4") (pintype "input"))
    )
    (net (code "192") (name "unconnected-(U3-A2-Pad3)") (class "Default")
      (node (ref "U3") (pin "3") (pinfunction "A2_3") (pintype "input"))
    )
    (net (code "193") (name "unconnected-(U3-A3-Pad2)") (class "Default")
      (node (ref "U3") (pin "2") (pinfunction "A3_2") (pintype "input"))
    )
    (net (code "194") (name "unconnected-(U3-A4-Pad1)") (class "Default")
      (node (ref "U3") (pin "1") (pinfunction "A4_1") (pintype "input"))
    )
    (net (code "195") (name "unconnected-(U3-A5-Pad44)") (class "Default")
      (node (ref "U3") (pin "44") (pinfunction "A5_44") (pintype "input"))
    )
    (net (code "196") (name "unconnected-(U3-A6-Pad43)") (class "Default")
      (node (ref "U3") (pin "43") (pinfunction "A6_43") (pintype "input"))
    )
    (net (code "197") (name "unconnected-(U3-A7-Pad42)") (class "Default")
      (node (ref "U3") (pin "42") (pinfunction "A7_42") (pintype "input"))
    )
    (net (code "198") (name "unconnected-(U3-A8-Pad27)") (class "Default")
      (node (ref "U3") (pin "27") (pinfunction "A8_27") (pintype "input"))
    )
    (net (code "199") (name "unconnected-(U3-A9-Pad26)") (class "Default")
      (node (ref "U3") (pin "26") (pinfunction "A9_26") (pintype "input"))
    )
    (net (code "200") (name "unconnected-(U3-A10-Pad25)") (class "Default")
      (node (ref "U3") (pin "25") (pinfunction "A10_25") (pintype "input"))
    )
    (net (code "201") (name "unconnected-(U3-A11-Pad24)") (class "Default")
      (node (ref "U3") (pin "24") (pinfunction "A11_24") (pintype "input"))
    )
    (net (code "202") (name "unconnected-(U3-A12-Pad22)") (class "Default")
      (node (ref "U3") (pin "22") (pinfunction "A12_22") (pintype "input"))
    )
    (net (code "203") (name "unconnected-(U3-A13-Pad21)") (class "Default")
      (node (ref "U3") (pin "21") (pinfunction "A13_21") (pintype "input"))
    )
    (net (code "204") (name "unconnected-(U3-A14-Pad20)") (class "Default")
      (node (ref "U3") (pin "20") (pinfunction "A14_20") (pintype "input"))
    )
    (net (code "205") (name "unconnected-(U3-A15-Pad19)") (class "Default")
      (node (ref "U3") (pin "19") (pinfunction "A15_19") (pintype "input"))
    )
    (net (code "206") (name "unconnected-(U3-A16-Pad18)") (class "Default")
      (node (ref "U3") (pin "18") (pinfunction "A16_18") (pintype "input"))
    )
    (net (code "207") (name "unconnected-(U3-A17-Pad23)") (class "Default")
      (node (ref "U3") (pin "23") (pinfunction "A17_23") (pintype "input"))
    )
    (net (code "208") (name "unconnected-(U3-A18-Pad28)") (class "Default")
      (node (ref "U3") (pin "28") (pinfunction "A18_28") (pintype "input"))
    )
    (net (code "209") (name "unconnected-(U3-CS1#-Pad6)") (class "Default")
      (node (ref "U3") (pin "6") (pinfunction "CS1#_6") (pintype "input"))
    )
    (net (code "210") (name "unconnected-(U3-I{slash}O0-Pad7)") (class "Default")
      (node (ref "U3") (pin "7") (pinfunction "I/O0_7") (pintype "input"))
    )
    (net (code "211") (name "unconnected-(U3-I{slash}O1-Pad8)") (class "Default")
      (node (ref "U3") (pin "8") (pinfunction "I/O1_8") (pintype "input"))
    )
    (net (code "212") (name "unconnected-(U3-I{slash}O2-Pad9)") (class "Default")
      (node (ref "U3") (pin "9") (pinfunction "I/O2_9") (pintype "input"))
    )
    (net (code "213") (name "unconnected-(U3-I{slash}O3-Pad10)") (class "Default")
      (node (ref "U3") (pin "10") (pinfunction "I/O3_10") (pintype "input"))
    )
    (net (code "214") (name "unconnected-(U3-I{slash}O4-Pad13)") (class "Default")
      (node (ref "U3") (pin "13") (pinfunction "I/O4_13") (pintype "input"))
    )
    (net (code "215") (name "unconnected-(U3-I{slash}O5-Pad14)") (class "Default")
      (node (ref "U3") (pin "14") (pinfunction "I/O5_14") (pintype "input"))
    )
    (net (code "216") (name "unconnected-(U3-I{slash}O6-Pad15)") (class "Default")
      (node (ref "U3") (pin "15") (pinfunction "I/O6_15") (pintype "input"))
    )
    (net (code "217") (name "unconnected-(U3-I{slash}O7-Pad16)") (class "Default")
      (node (ref "U3") (pin "16") (pinfunction "I/O7_16") (pintype "input"))
    )
    (net (code "218") (name "unconnected-(U3-I{slash}O8-Pad29)") (class "Default")
      (node (ref "U3") (pin "29") (pinfunction "I/O8_29") (pintype "input"))
    )
    (net (code "219") (name "unconnected-(U3-I{slash}O9-Pad30)") (class "Default")
      (node (ref "U3") (pin "30") (pinfunction "I/O9_30") (pintype "input"))
    )
    (net (code "220") (name "unconnected-(U3-I{slash}O10-Pad31)") (class "Default")
      (node (ref "U3") (pin "31") (pinfunction "I/O10_31") (pintype "input"))
    )
    (net (code "221") (name "unconnected-(U3-I{slash}O11-Pad32)") (class "Default")
      (node (ref "U3") (pin "32") (pinfunction "I/O11_32") (pintype "input"))
    )
    (net (code "222") (name "unconnected-(U3-I{slash}O12-Pad35)") (class "Default")
      (node (ref "U3") (pin "35") (pinfunction "I/O12_35") (pintype "input"))
    )
    (net (code "223") (name "unconnected-(U3-I{slash}O13-Pad36)") (class "Default")
      (node (ref "U3") (pin "36") (pinfunction "I/O13_36") (pintype "input"))
    )
    (net (code "224") (name "unconnected-(U3-I{slash}O14-Pad37)") (class "Default")
      (node (ref "U3") (pin "37") (pinfunction "I/O14_37") (pintype "input"))
    )
    (net (code "225") (name "unconnected-(U3-I{slash}O15-Pad38)") (class "Default")
      (node (ref "U3") (pin "38") (pinfunction "I/O15_38") (pintype "input"))
    )
    (net (code "226") (name "unconnected-(U3-LB#-Pad39)") (class "Default")
      (node (ref "U3") (pin "39") (pinfunction "LB#_39") (pintype "input"))
    )
    (net (code "227") (name "unconnected-(U3-OE#-Pad41)") (class "Default")
      (node (ref "U3") (pin "41") (pinfunction "OE#_41") (pintype "input"))
    )
    (net (code "228") (name "unconnected-(U3-UB#-Pad40)") (class "Default")
      (node (ref "U3") (pin "40") (pinfunction "UB#_40") (pintype "input"))
    )
    (net (code "229") (name "unconnected-(U3-WE#-Pad17)") (class "Default")
      (node (ref "U3") (pin "17") (pinfunction "WE#_17") (pintype "input"))
    )
    (net (code "230") (name "unconnected-(U4-EP-Pad9)") (class "Default")
      (node (ref "U4") (pin "9") (pinfunction "EP_9") (pintype "input"))
    )
  )
)
